# RS485_BUS.net
KiCad netlist of a schematic drawn in Altium Designer
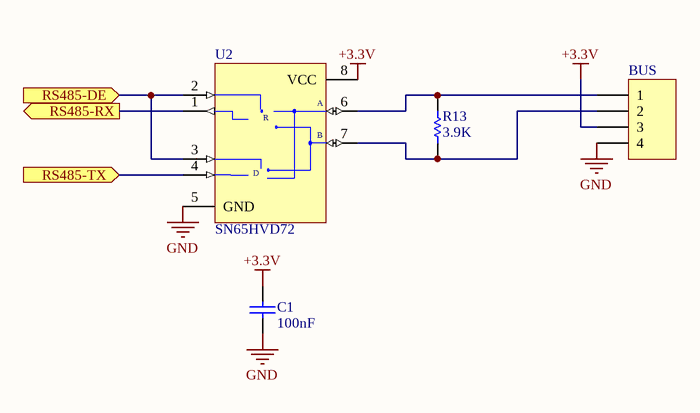
[diagram p0: RS485 BUS.SchDoc]

(export (version "E")
  (design (tool "Eeschema 10.0.6"))
  (components
    (comp (ref "BUS")
      (value "BUS SOCKET")
      (footprint "PH-4")
      (fields (field (name "PUBLISHER") "Altium Limited"))
      (libsource (lib "Miscellaneous Connectors") (part "Header 4"))
    )
    (comp (ref "C1")
      (value "100nF")
      (footprint "C603")
      (description "Capacitor")
      (fields (field (name "DESIGNER") "Parsa Malekpour"))
      (libsource (lib "UserPKG") (part "Cap"))
    )
    (comp (ref "R13")
      (value "3.9K")
      (footprint "R805")
      (description "Resistor")
      (fields (field (name "DESIGNER") "Parsa Malekpour"))
      (libsource (lib "UserPKG") (part "Resistor"))
    )
    (comp (ref "U2")
      (value "SN65HVD72")
      (footprint "SOIC-8N")
      (description "3.3-V Supply RS-485 With IEC ESD protection")
      (fields (field (name "PUBLISHER") "Altium Limited"))
      (libsource (lib "UserPKG") (part "SN65HVD72"))
    )
  )
  (nets
    (net (code "1") (name "+3.3V") (class "Default")
      (node (ref "BUS") (pin "3") (pinfunction "3_3") (pintype "passive"))
      (node (ref "C1") (pin "2") (pinfunction "2_2") (pintype "passive"))
      (node (ref "U2") (pin "8") (pinfunction "VCC_8") (pintype "power_in"))
    )
    (net (code "2") (name "/RS485-DE") (class "Default")
      (node (ref "U2") (pin "2") (pinfunction "~{RE}_2") (pintype "input"))
      (node (ref "U2") (pin "3") (pinfunction "DE_3") (pintype "input"))
    )
    (net (code "3") (name "/RS485-RX") (class "Default")
      (node (ref "U2") (pin "1") (pinfunction "RO_1") (pintype "output"))
    )
    (net (code "4") (name "/RS485-TX") (class "Default")
      (node (ref "U2") (pin "4") (pinfunction "DI_4") (pintype "input"))
    )
    (net (code "5") (name "GND") (class "Default")
      (node (ref "BUS") (pin "4") (pinfunction "4_4") (pintype "passive"))
      (node (ref "C1") (pin "1") (pinfunction "1_1") (pintype "passive"))
      (node (ref "U2") (pin "5") (pinfunction "GND_5") (pintype "power_in"))
    )
    (net (code "6") (name "Net-(U2-A)") (class "Default")
      (node (ref "BUS") (pin "1") (pinfunction "1_1") (pintype "passive"))
      (node (ref "R13") (pin "2") (pinfunction "2_2") (pintype "passive"))
      (node (ref "U2") (pin "6") (pinfunction "A_6") (pintype "bidirectional"))
    )
    (net (code "7") (name "Net-(U2-B)") (class "Default")
      (node (ref "BUS") (pin "2") (pinfunction "2_2") (pintype "passive"))
      (node (ref "R13") (pin "1") (pinfunction "1_1") (pintype "passive"))
      (node (ref "U2") (pin "7") (pinfunction "B_7") (pintype "bidirectional"))
    )
  )
)
